# touch-tara-h66.net
KiCad netlist of a schematic drawn in Altium Designer
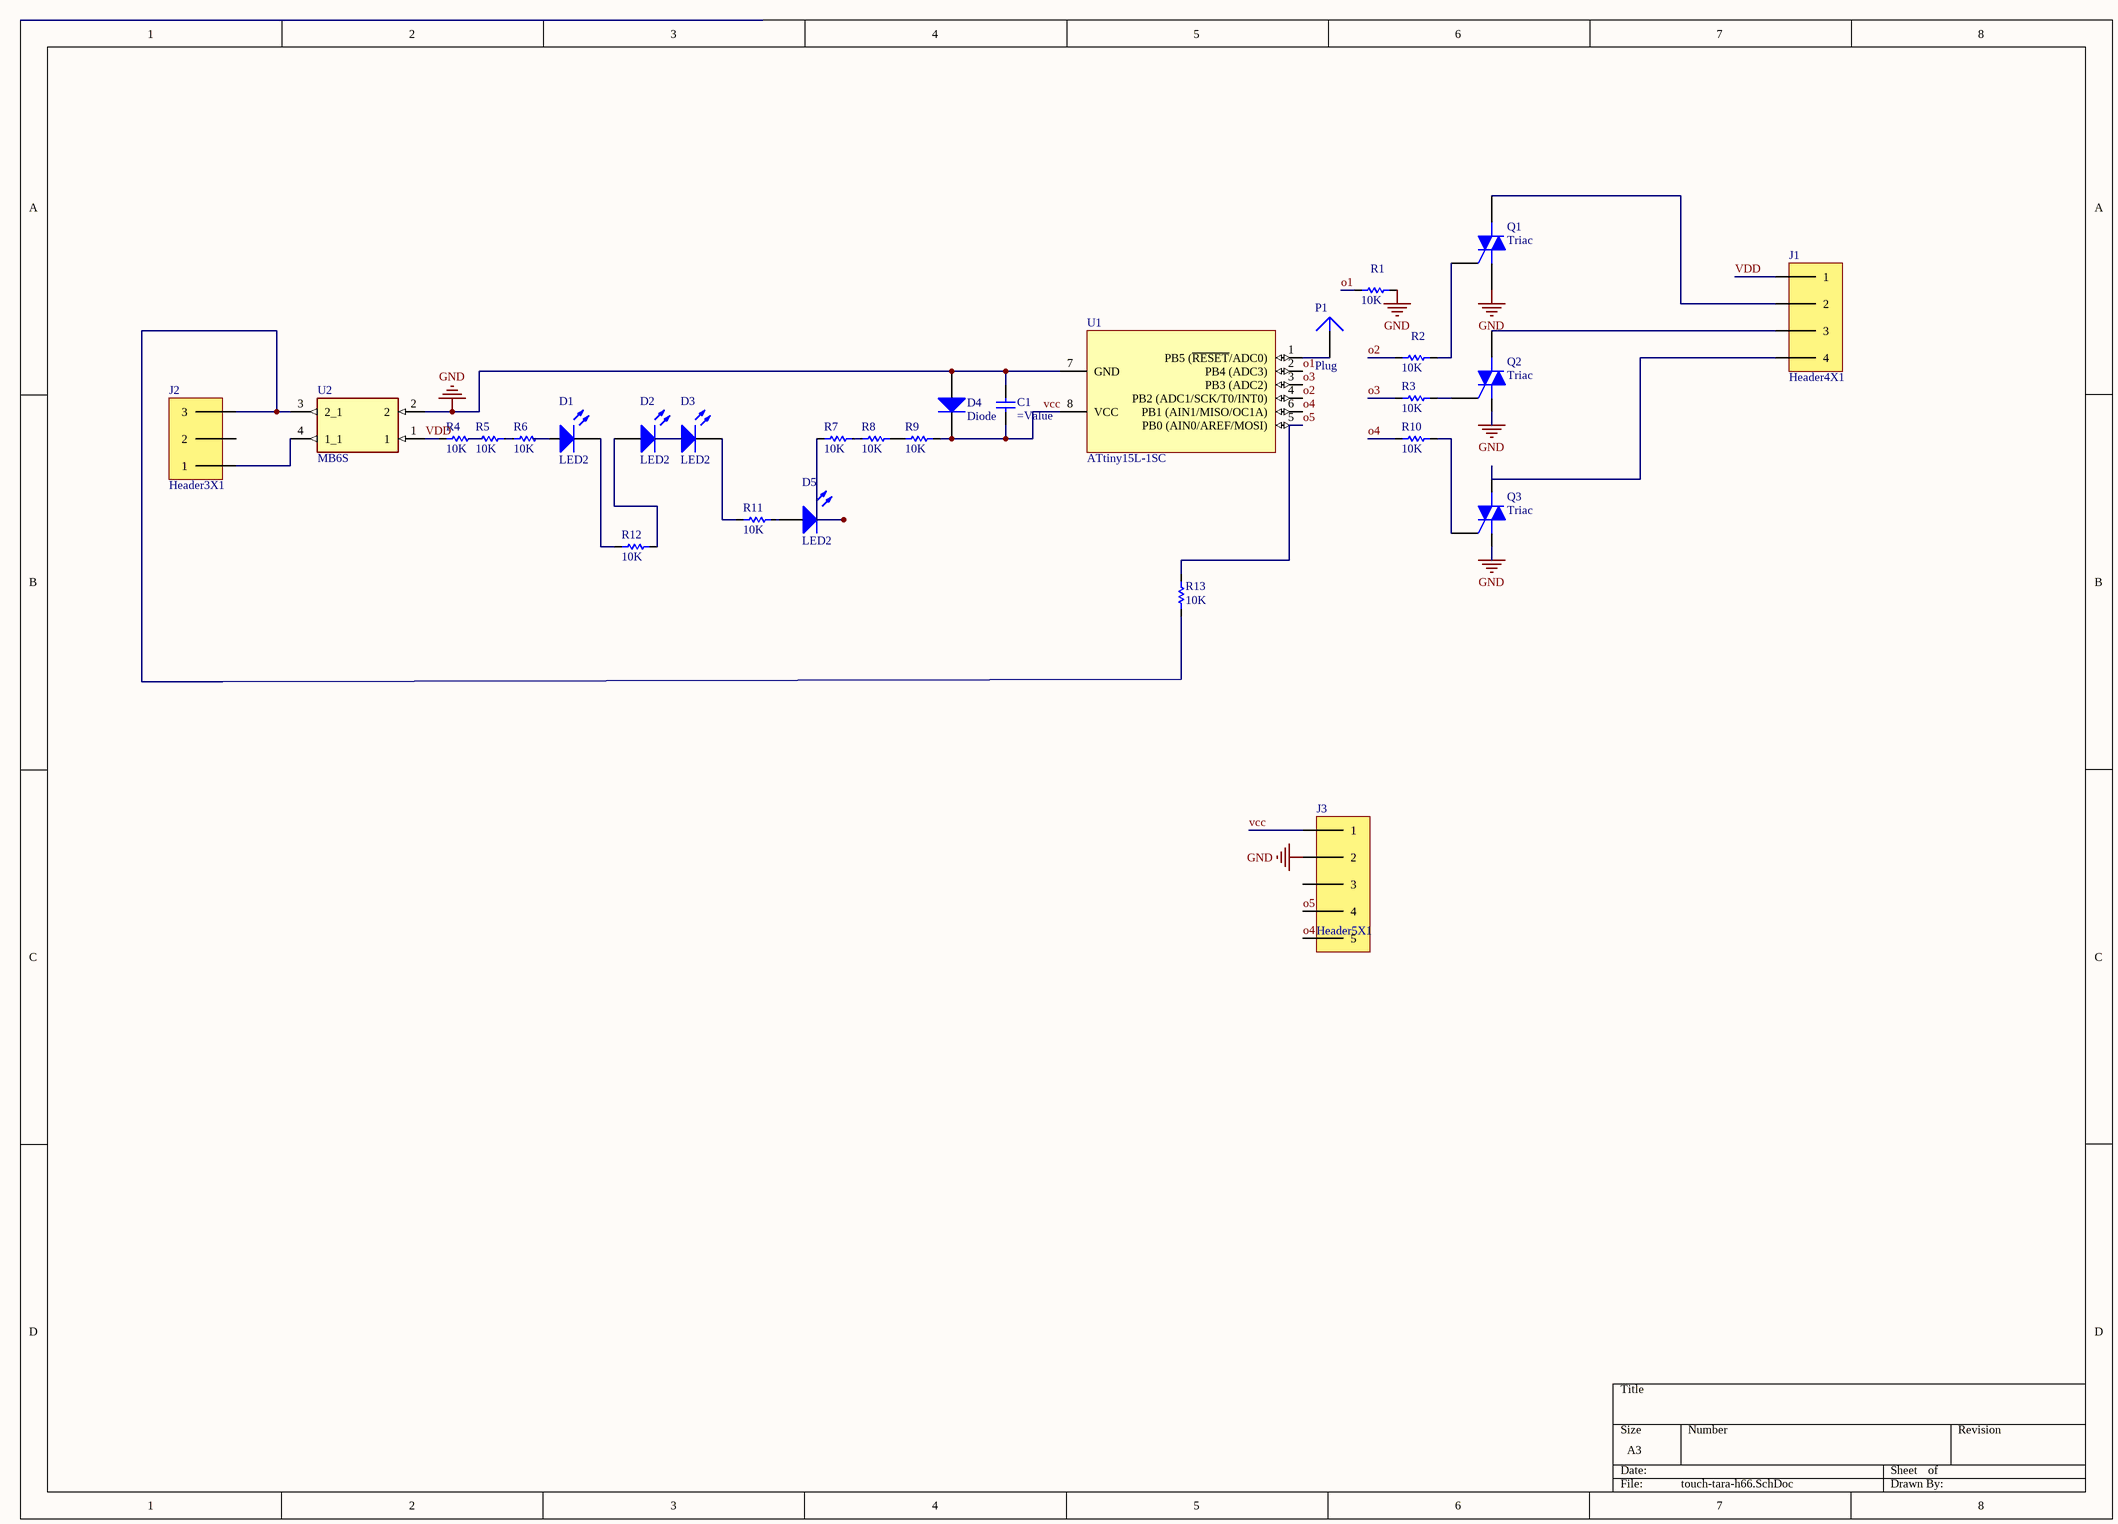
[diagram p0: touch-tara-h66.SchDoc]

(export (version "E")
  (design (tool "Eeschema 10.0.6"))
  (components
    (comp (ref "C1")
      (value "~")
      (footprint "CAP 1206")
      (description "Capacitor")
      (libsource (lib "AltiumLib1") (part "Capacitor"))
    )
    (comp (ref "D1")
      (value "LED2")
      (footprint "3.2X1.6X1.1")
      (description "Typical RED, GREEN, YELLOW, AMBER GaAs LED")
      (fields (field (name "PUBLISHER") "Altium Limited"))
      (libsource (lib "Miscellaneous Devices") (part "LED2"))
    )
    (comp (ref "D2")
      (value "LED2")
      (footprint "3.2X1.6X1.1")
      (description "Typical RED, GREEN, YELLOW, AMBER GaAs LED")
      (fields (field (name "PUBLISHER") "Altium Limited"))
      (libsource (lib "Miscellaneous Devices") (part "LED2"))
    )
    (comp (ref "D3")
      (value "LED2")
      (footprint "3.2X1.6X1.1")
      (description "Typical RED, GREEN, YELLOW, AMBER GaAs LED")
      (fields (field (name "PUBLISHER") "Altium Limited"))
      (libsource (lib "Miscellaneous Devices") (part "LED2"))
    )
    (comp (ref "D4")
      (value "Diode")
      (footprint "C1206")
      (description "Default Diode")
      (fields (field (name "PUBLISHER") "Altium Limited"))
      (libsource (lib "Miscellaneous Devices") (part "Diode"))
    )
    (comp (ref "D5")
      (value "LED2")
      (footprint "3.2X1.6X1.1")
      (description "Typical RED, GREEN, YELLOW, AMBER GaAs LED")
      (fields (field (name "PUBLISHER") "Altium Limited"))
      (libsource (lib "Miscellaneous Devices") (part "LED2"))
    )
    (comp (ref "J1")
      (value "Header4X1")
      (footprint "HEADER 4X1")
      (libsource (lib "AltiumLib1") (part "Header4X1"))
    )
    (comp (ref "J2")
      (value "Header3X1")
      (footprint "HEADER 3X1")
      (libsource (lib "AltiumLib1") (part "Header3X1"))
    )
    (comp (ref "J3")
      (value "Header5X1")
      (footprint "HEADER 5X1")
      (libsource (lib "AltiumLib1") (part "Header5X1"))
    )
    (comp (ref "P1")
      (value "Plug")
      (footprint "PIN1")
      (fields (field (name "PUBLISHER") "Altium Limited"))
      (libsource (lib "Miscellaneous Connectors") (part "Plug"))
    )
    (comp (ref "Q1")
      (value "Triac")
      (footprint "SOT89N")
      (description "Silicon Bidirectional Triode Thyristor")
      (fields (field (name "PUBLISHER") "Altium Limited"))
      (libsource (lib "Miscellaneous Devices") (part "Triac"))
    )
    (comp (ref "Q2")
      (value "Triac")
      (footprint "SOT89N")
      (description "Silicon Bidirectional Triode Thyristor")
      (fields (field (name "PUBLISHER") "Altium Limited"))
      (libsource (lib "Miscellaneous Devices") (part "Triac"))
    )
    (comp (ref "Q3")
      (value "Triac")
      (footprint "SOT89N")
      (description "Silicon Bidirectional Triode Thyristor")
      (fields (field (name "PUBLISHER") "Altium Limited"))
      (libsource (lib "Miscellaneous Devices") (part "Triac"))
    )
    (comp (ref "R1")
      (value "10K")
      (footprint "RES 1206 (3216X08L)")
      (description "Resistor")
      (fields (field (name "TOLERANCE") "5%") (field (name "POWER") "1/4 W"))
      (libsource (lib "AltiumLib1") (part "Resistor"))
    )
    (comp (ref "R2")
      (value "10K")
      (footprint "RES 1206 (3216X08L)")
      (description "Resistor")
      (fields (field (name "TOLERANCE") "5%") (field (name "POWER") "1/4 W"))
      (libsource (lib "AltiumLib1") (part "Resistor"))
    )
    (comp (ref "R3")
      (value "10K")
      (footprint "RES 1206 (3216X08L)")
      (description "Resistor")
      (fields (field (name "TOLERANCE") "5%") (field (name "POWER") "1/4 W"))
      (libsource (lib "AltiumLib1") (part "Resistor"))
    )
    (comp (ref "R4")
      (value "10K")
      (footprint "RES 2010 (5026X08L)")
      (description "Resistor")
      (fields (field (name "TOLERANCE") "5%") (field (name "POWER") "1/4 W"))
      (libsource (lib "AltiumLib1") (part "Resistor"))
    )
    (comp (ref "R5")
      (value "10K")
      (footprint "RES 2010 (5026X08L)")
      (description "Resistor")
      (fields (field (name "TOLERANCE") "5%") (field (name "POWER") "1/4 W"))
      (libsource (lib "AltiumLib1") (part "Resistor"))
    )
    (comp (ref "R6")
      (value "10K")
      (footprint "RES 2010 (5026X08L)")
      (description "Resistor")
      (fields (field (name "TOLERANCE") "5%") (field (name "POWER") "1/4 W"))
      (libsource (lib "AltiumLib1") (part "Resistor"))
    )
    (comp (ref "R7")
      (value "10K")
      (footprint "RES 2010 (5026X08L)")
      (description "Resistor")
      (fields (field (name "TOLERANCE") "5%") (field (name "POWER") "1/4 W"))
      (libsource (lib "AltiumLib1") (part "Resistor"))
    )
    (comp (ref "R8")
      (value "10K")
      (footprint "RES 2010 (5026X08L)")
      (description "Resistor")
      (fields (field (name "TOLERANCE") "5%") (field (name "POWER") "1/4 W"))
      (libsource (lib "AltiumLib1") (part "Resistor"))
    )
    (comp (ref "R9")
      (value "10K")
      (footprint "RES 2010 (5026X08L)")
      (description "Resistor")
      (fields (field (name "TOLERANCE") "5%") (field (name "POWER") "1/4 W"))
      (libsource (lib "AltiumLib1") (part "Resistor"))
    )
    (comp (ref "R10")
      (value "10K")
      (footprint "RES 1206 (3216X08L)")
      (description "Resistor")
      (fields (field (name "TOLERANCE") "5%") (field (name "POWER") "1/4 W"))
      (libsource (lib "AltiumLib1") (part "Resistor"))
    )
    (comp (ref "R11")
      (value "10K")
      (footprint "RES 2010 (5026X08L)")
      (description "Resistor")
      (fields (field (name "TOLERANCE") "5%") (field (name "POWER") "1/4 W"))
      (libsource (lib "AltiumLib1") (part "Resistor"))
    )
    (comp (ref "R12")
      (value "10K")
      (footprint "RES 2010 (5026X08L)")
      (description "Resistor")
      (fields (field (name "TOLERANCE") "5%") (field (name "POWER") "1/4 W"))
      (libsource (lib "AltiumLib1") (part "Resistor"))
    )
    (comp (ref "R13")
      (value "10K")
      (footprint "RES 1206 (3216X08L)")
      (description "Resistor")
      (fields (field (name "TOLERANCE") "5%") (field (name "POWER") "1/4 W"))
      (libsource (lib "AltiumLib1") (part "Resistor"))
    )
    (comp (ref "U1")
      (value "ATtiny15L-1SC")
      (footprint "8S2_N")
      (description "8-Bit AVR Microcontroller with 1K Byte of Flash Memory")
      (fields (field (name "PUBLISHER") "Altium Limited"))
      (libsource (lib "Atmel Microcontroller 8-Bit AVR") (part "ATtiny15L-1SC"))
    )
    (comp (ref "U2")
      (value "MB6S")
      (footprint "SOIC245P670X270-4N")
      (description "Bridge Rectifier Single Phase Standard 600V Surface Mount 4-SOIC")
      (fields (field (name "MF") "ON Semiconductor") (field (name "DIGI-KEY_PART_NUMBER") "MB6SCT-ND"))
      (libsource (lib "MB6S") (part "MB6S"))
    )
  )
  (nets
    (net (code "1") (name "/VDD") (class "Default")
      (node (ref "J1") (pin "1") (pinfunction "1_1") (pintype "passive"))
      (node (ref "R4") (pin "1") (pinfunction "1_1") (pintype "passive"))
      (node (ref "U2") (pin "1") (pinfunction "1_1") (pintype "input"))
    )
    (net (code "2") (name "/o1") (class "Default")
      (node (ref "R1") (pin "1") (pinfunction "1_1") (pintype "passive"))
      (node (ref "U1") (pin "2") (pinfunction "PB4_(ADC3)_2") (pintype "bidirectional"))
    )
    (net (code "3") (name "/o2") (class "Default")
      (node (ref "R2") (pin "1") (pinfunction "1_1") (pintype "passive"))
      (node (ref "U1") (pin "4") (pinfunction "PB2_(ADC1/SCK/T0/INT0)_4") (pintype "bidirectional"))
    )
    (net (code "4") (name "/o3") (class "Default")
      (node (ref "R3") (pin "1") (pinfunction "1_1") (pintype "passive"))
      (node (ref "U1") (pin "3") (pinfunction "PB3_(ADC2)_3") (pintype "bidirectional"))
    )
    (net (code "5") (name "/o4") (class "Default")
      (node (ref "J3") (pin "5") (pinfunction "5_5") (pintype "passive"))
      (node (ref "R10") (pin "1") (pinfunction "1_1") (pintype "passive"))
      (node (ref "U1") (pin "6") (pinfunction "PB1_(AIN1/MISO/OC1A)_6") (pintype "bidirectional"))
    )
    (net (code "6") (name "/o5") (class "Default")
      (node (ref "J3") (pin "4") (pinfunction "4_4") (pintype "passive"))
      (node (ref "R13") (pin "2") (pinfunction "2_2") (pintype "passive"))
      (node (ref "U1") (pin "5") (pinfunction "PB0_(AIN0/AREF/MOSI)_5") (pintype "bidirectional"))
    )
    (net (code "7") (name "/vcc") (class "Default")
      (node (ref "C1") (pin "1") (pinfunction "+_1") (pintype "passive"))
      (node (ref "D4") (pin "2") (pinfunction "K_2") (pintype "passive"))
      (node (ref "J3") (pin "1") (pinfunction "1_1") (pintype "passive"))
      (node (ref "R9") (pin "2") (pinfunction "2_2") (pintype "passive"))
      (node (ref "U1") (pin "8") (pinfunction "VCC_8") (pintype "power_in"))
    )
    (net (code "8") (name "GND") (class "Default")
      (node (ref "C1") (pin "2") (pinfunction "-_2") (pintype "passive"))
      (node (ref "D4") (pin "1") (pinfunction "A_1") (pintype "passive"))
      (node (ref "J3") (pin "2") (pinfunction "2_2") (pintype "passive"))
      (node (ref "Q1") (pin "1") (pinfunction "M1_1") (pintype "passive"))
      (node (ref "Q2") (pin "1") (pinfunction "M1_1") (pintype "passive"))
      (node (ref "Q3") (pin "1") (pinfunction "M1_1") (pintype "passive"))
      (node (ref "R1") (pin "2") (pinfunction "2_2") (pintype "passive"))
      (node (ref "U1") (pin "7") (pinfunction "GND_7") (pintype "power_in"))
      (node (ref "U2") (pin "2") (pinfunction "2_2") (pintype "input"))
    )
    (net (code "9") (name "Net-(D1-A)") (class "Default")
      (node (ref "D1") (pin "1") (pinfunction "A_1") (pintype "passive"))
      (node (ref "R6") (pin "2") (pinfunction "2_2") (pintype "passive"))
    )
    (net (code "10") (name "Net-(D1-K)") (class "Default")
      (node (ref "D1") (pin "2") (pinfunction "K_2") (pintype "passive"))
      (node (ref "R12") (pin "1") (pinfunction "1_1") (pintype "passive"))
    )
    (net (code "11") (name "Net-(D2-A)") (class "Default")
      (node (ref "D2") (pin "1") (pinfunction "A_1") (pintype "passive"))
      (node (ref "R12") (pin "2") (pinfunction "2_2") (pintype "passive"))
    )
    (net (code "12") (name "Net-(D2-K)") (class "Default")
      (node (ref "D2") (pin "2") (pinfunction "K_2") (pintype "passive"))
      (node (ref "D3") (pin "1") (pinfunction "A_1") (pintype "passive"))
    )
    (net (code "13") (name "Net-(D3-K)") (class "Default")
      (node (ref "D3") (pin "2") (pinfunction "K_2") (pintype "passive"))
      (node (ref "R11") (pin "1") (pinfunction "1_1") (pintype "passive"))
    )
    (net (code "14") (name "Net-(D5-A)") (class "Default")
      (node (ref "D5") (pin "1") (pinfunction "A_1") (pintype "passive"))
      (node (ref "R11") (pin "2") (pinfunction "2_2") (pintype "passive"))
    )
    (net (code "15") (name "Net-(D5-K)") (class "Default")
      (node (ref "D5") (pin "2") (pinfunction "K_2") (pintype "passive"))
      (node (ref "R7") (pin "1") (pinfunction "1_1") (pintype "passive"))
    )
    (net (code "16") (name "Net-(Q1-G)") (class "Default")
      (node (ref "Q1") (pin "3") (pinfunction "G_3") (pintype "passive"))
      (node (ref "R2") (pin "2") (pinfunction "2_2") (pintype "passive"))
    )
    (net (code "17") (name "Net-(Q1-M2)") (class "Default")
      (node (ref "J1") (pin "2") (pinfunction "2_2") (pintype "passive"))
      (node (ref "Q1") (pin "2") (pinfunction "M2_2") (pintype "passive"))
    )
    (net (code "18") (name "Net-(Q2-G)") (class "Default")
      (node (ref "Q2") (pin "3") (pinfunction "G_3") (pintype "passive"))
      (node (ref "R3") (pin "2") (pinfunction "2_2") (pintype "passive"))
    )
    (net (code "19") (name "Net-(Q2-M2)") (class "Default")
      (node (ref "J1") (pin "3") (pinfunction "3_3") (pintype "passive"))
      (node (ref "Q2") (pin "2") (pinfunction "M2_2") (pintype "passive"))
    )
    (net (code "20") (name "Net-(Q3-G)") (class "Default")
      (node (ref "Q3") (pin "3") (pinfunction "G_3") (pintype "passive"))
      (node (ref "R10") (pin "2") (pinfunction "2_2") (pintype "passive"))
    )
    (net (code "21") (name "Net-(Q3-M2)") (class "Default")
      (node (ref "J1") (pin "4") (pinfunction "4_4") (pintype "passive"))
      (node (ref "Q3") (pin "2") (pinfunction "M2_2") (pintype "passive"))
    )
    (net (code "22") (name "Net-(R4-Pad2)") (class "Default")
      (node (ref "R4") (pin "2") (pinfunction "2_2") (pintype "passive"))
      (node (ref "R5") (pin "1") (pinfunction "1_1") (pintype "passive"))
    )
    (net (code "23") (name "Net-(R5-Pad2)") (class "Default")
      (node (ref "R5") (pin "2") (pinfunction "2_2") (pintype "passive"))
      (node (ref "R6") (pin "1") (pinfunction "1_1") (pintype "passive"))
    )
    (net (code "24") (name "Net-(R7-Pad2)") (class "Default")
      (node (ref "R7") (pin "2") (pinfunction "2_2") (pintype "passive"))
      (node (ref "R8") (pin "1") (pinfunction "1_1") (pintype "passive"))
    )
    (net (code "25") (name "Net-(R8-Pad2)") (class "Default")
      (node (ref "R8") (pin "2") (pinfunction "2_2") (pintype "passive"))
      (node (ref "R9") (pin "1") (pinfunction "1_1") (pintype "passive"))
    )
    (net (code "26") (name "Net-(U1-PB5_(~{RESET}{slash}ADC0))") (class "Default")
      (node (ref "P1") (pin "1") (pinfunction "1_1") (pintype "passive"))
      (node (ref "U1") (pin "1") (pinfunction "PB5_(~{RESET}/ADC0)_1") (pintype "bidirectional"))
    )
    (net (code "27") (name "Net-(U2-1_1)") (class "Default")
      (node (ref "J2") (pin "1") (pinfunction "1_1") (pintype "passive"))
      (node (ref "U2") (pin "4") (pinfunction "1_1_4") (pintype "output"))
    )
    (net (code "28") (name "Net-(U2-2_1)") (class "Default")
      (node (ref "J2") (pin "3") (pinfunction "3_3") (pintype "passive"))
      (node (ref "R13") (pin "1") (pinfunction "1_1") (pintype "passive"))
      (node (ref "U2") (pin "3") (pinfunction "2_1_3") (pintype "output"))
    )
    (net (code "29") (name "unconnected-(J2-Pad2)") (class "Default")
      (node (ref "J2") (pin "2") (pinfunction "2_2") (pintype "passive"))
    )
    (net (code "30") (name "unconnected-(J3-Pad3)") (class "Default")
      (node (ref "J3") (pin "3") (pinfunction "3_3") (pintype "passive"))
    )
  )
)
